# Gas_Sampler-9V_Boost.net
KiCad netlist of a schematic drawn in Altium Designer
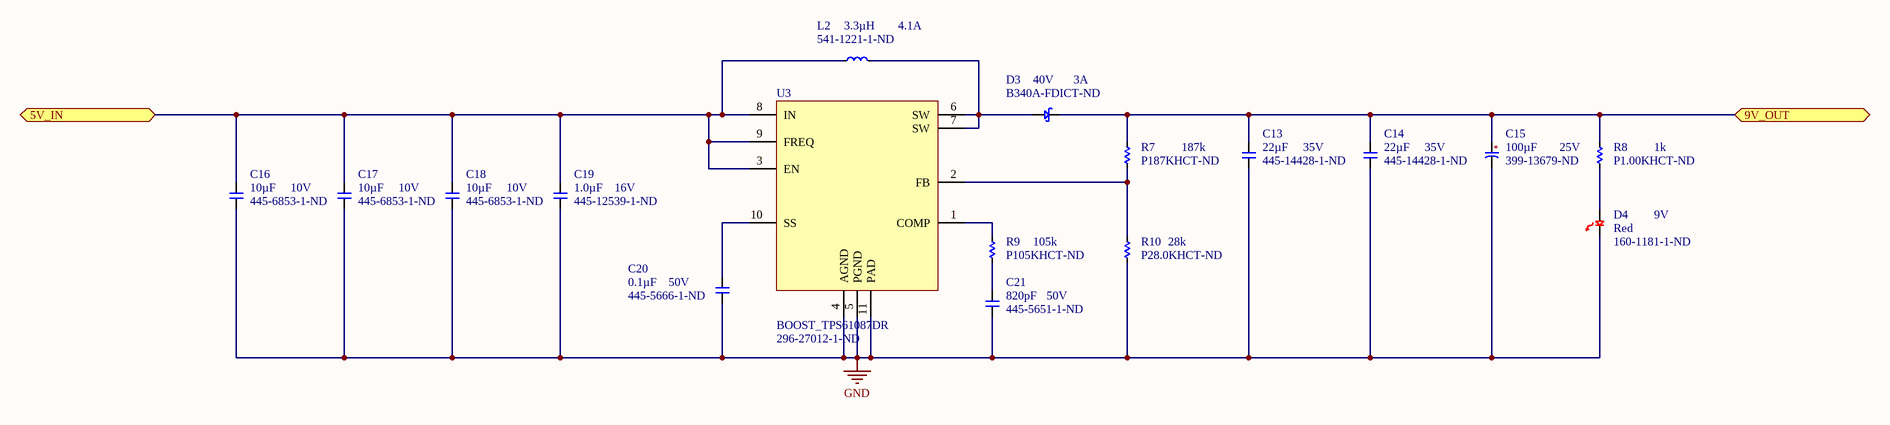
[diagram p0: Gas_Sampler-9V_Boost.SchDoc]

(export (version "E")
  (design (tool "Eeschema 10.0.6"))
  (components
    (comp (ref "C13")
      (value "22µF")
      (footprint "C0805")
      (description "CAP CER 22UF 35V 20% X5R 0805")
      (fields
        (field (name "MANUFACTURER") "TDK Corporation")
        (field (name "MANUFACTURER PART NUMBER") "C2012X5R1V226M125AC")
        (field (name "SUPPLIER PART NUMBER 1") "445-14428-1-ND")
        (field (name "VOLTAGE - RATED") "35V")
      )
      (libsource (lib "capacitor") (part "CAP_CER_0805_22UF_35V_20%_X5R"))
    )
    (comp (ref "C14")
      (value "22µF")
      (footprint "C0805")
      (description "CAP CER 22UF 35V 20% X5R 0805")
      (fields
        (field (name "MANUFACTURER") "TDK Corporation")
        (field (name "MANUFACTURER PART NUMBER") "C2012X5R1V226M125AC")
        (field (name "SUPPLIER PART NUMBER 1") "445-14428-1-ND")
        (field (name "VOLTAGE - RATED") "35V")
      )
      (libsource (lib "capacitor") (part "CAP_CER_0805_22UF_35V_20%_X5R"))
    )
    (comp (ref "C15")
      (value "100µF")
      (footprint "CAP_RADIAL_8MM_DIA_9MM_LEN_3.5MM_LEADSPACE")
      (description "CAP ALUM POLY 100UF 20% 25V T/H")
      (fields
        (field (name "MANUFACTURER") "KEMET")
        (field (name "MANUFACTURER PART NUMBER") "A750KK107M1EAAE040")
        (field (name "SUPPLIER PART NUMBER 1") "399-13679-ND")
        (field (name "VOLTAGE") "25V")
      )
      (libsource (lib "capacitor") (part "CAP_POLYMER_100UF_25V_20%_8X9MM_TH"))
    )
    (comp (ref "C16")
      (value "10µF")
      (footprint "C0603")
      (description "CAP CER 10UF 10V X5R 0603")
      (fields
        (field (name "MANUFACTURER") "TDK Corporation")
        (field (name "MANUFACTURER PART NUMBER") "C1608X5R1A106M080AC")
        (field (name "VOLTAGE - RATED") "10V")
        (field (name "SUPPLIER PART NUMBER 1") "445-6853-1-ND")
      )
      (libsource (lib "capacitor") (part "CAP_CER_0603_10UF_10V_20%_X5R"))
    )
    (comp (ref "C17")
      (value "10µF")
      (footprint "C0603")
      (description "CAP CER 10UF 10V X5R 0603")
      (fields
        (field (name "MANUFACTURER") "TDK Corporation")
        (field (name "MANUFACTURER PART NUMBER") "C1608X5R1A106M080AC")
        (field (name "VOLTAGE - RATED") "10V")
        (field (name "SUPPLIER PART NUMBER 1") "445-6853-1-ND")
      )
      (libsource (lib "capacitor") (part "CAP_CER_0603_10UF_10V_20%_X5R"))
    )
    (comp (ref "C18")
      (value "10µF")
      (footprint "C0603")
      (description "CAP CER 10UF 10V X5R 0603")
      (fields
        (field (name "MANUFACTURER") "TDK Corporation")
        (field (name "MANUFACTURER PART NUMBER") "C1608X5R1A106M080AC")
        (field (name "VOLTAGE - RATED") "10V")
        (field (name "SUPPLIER PART NUMBER 1") "445-6853-1-ND")
      )
      (libsource (lib "capacitor") (part "CAP_CER_0603_10UF_10V_20%_X5R"))
    )
    (comp (ref "C19")
      (value "1.0µF")
      (footprint "C0603")
      (description "CAP CER 1UF 16V 10% X7R 0603")
      (fields
        (field (name "MANUFACTURER") "TDK Corporation")
        (field (name "MANUFACTURER PART NUMBER") "CGA3E1X7R1C105K080AC")
        (field (name "SUPPLIER PART NUMBER 1") "445-12539-1-ND")
        (field (name "VOLTAGE - RATED") "16V")
      )
      (libsource (lib "capacitor") (part "CAP_CER_0603_1UF_16V_10%_X7R"))
    )
    (comp (ref "C20")
      (value "0.1µF")
      (footprint "C0603")
      (description "CAP CER 0.1UF 50V 10% X7R 0603")
      (fields
        (field (name "MANUFACTURER") "TDK Corporation")
        (field (name "MANUFACTURER PART NUMBER") "CGA3E2X7R1H104K080AA")
        (field (name "VOLTAGE - RATED") "50V")
        (field (name "SUPPLIER PART NUMBER 1") "445-5666-1-ND")
      )
      (libsource (lib "capacitor") (part "CAP_CER_0603_0.1UF_50V_10%_X7R"))
    )
    (comp (ref "C21")
      (value "820pF")
      (footprint "C0603")
      (description "CAP CER 820PF 50V C0G 0603")
      (fields
        (field (name "MANUFACTURER") "TDK Corporation")
        (field (name "MANUFACTURER PART NUMBER") "CGA3E2C0G1H821J080AA")
        (field (name "VOLTAGE - RATED") "50V")
        (field (name "SUPPLIER PART NUMBER 1") "445-5651-1-ND")
      )
      (libsource (lib "capacitor") (part "CAP_CER_0603_820PF_50V_5%_C0G/NP0"))
    )
    (comp (ref "D3")
      (value "SCHOTTKY_40V_3A_B340A-13-F")
      (footprint "SMA")
      (description "DIODE SCHOTTKY 3A 40V SMA")
      (fields
        (field (name "MANUFACTURER") "Diodes Inc")
        (field (name "MANUFACTURER PART NUMBER") "B340A-13-F")
        (field (name "SUPPLIER PART NUMBER 1") "B340A-FDICT-ND")
        (field (name "VOLTAGE - DC REVERSE (VR) (MAX)") "40V")
        (field (name "CURRENT - AVERAGE RECTIFIED (IO)") "3A")
      )
      (libsource (lib "diode") (part "SCHOTTKY_40V_3A_B340A-13-F"))
    )
    (comp (ref "D4")
      (value "9V")
      (footprint "LED_0603_RED")
      (description "LED RED CLEAR 0603 SMD")
      (fields
        (field (name "MANUFACTURER") "Lite-On Inc")
        (field (name "MANUFACTURER PART NUMBER") "LTST-C190CKT")
        (field (name "SUPPLIER PART NUMBER 1") "160-1181-1-ND")
        (field (name "COLOR") "Red")
      )
      (libsource (lib "diode") (part "LED_0603_RED_LR_LTST-C190CKT"))
    )
    (comp (ref "L2")
      (value "3.3µH")
      (footprint "INDUCTOR_IHLP2020_2MM_HEIGHT")
      (description "FIXED IND 3.3UH 4.1A 57.8 MOHM")
      (fields
        (field (name "MANUFACTURER") "Vishay Dale")
        (field (name "MANUFACTURER PART NUMBER") "IHLP2020BZER3R3M11")
        (field (name "CURRENT RATING") "4.1A")
        (field (name "SUPPLIER PART NUMBER 1") "541-1221-1-ND")
      )
      (libsource (lib "inductor") (part "IND_3.3UH_4.1A_IHLP2020BZER3R3M11"))
    )
    (comp (ref "R7")
      (value "187k")
      (footprint "R0603")
      (description "RES 187K OHM 1% 1/10W 0603")
      (fields
        (field (name "MANUFACTURER") "Panasonic Electronic Components")
        (field (name "MANUFACTURER PART NUMBER") "ERJ-3EKF1873V")
        (field (name "SUPPLIER PART NUMBER 1") "P187KHCT-ND")
      )
      (libsource (lib "resistor") (part "RES_0603_187K_OHMS_1/10W_1%"))
    )
    (comp (ref "R8")
      (value "1k")
      (footprint "R0603")
      (description "RES 1K OHM 1/10W 1% 0603 SMD")
      (fields
        (field (name "MANUFACTURER") "Panasonic Electronic Components")
        (field (name "MANUFACTURER PART NUMBER") "ERJ-3EKF1001V")
        (field (name "SUPPLIER PART NUMBER 1") "P1.00KHCT-ND")
      )
      (libsource (lib "resistor") (part "RES_0603_1K_OHM_1/10W_1%"))
    )
    (comp (ref "R9")
      (value "105k")
      (footprint "R0603")
      (description "RES 105K OHM 1% 1/10W 0603")
      (fields
        (field (name "MANUFACTURER") "Panasonic Electronic Components")
        (field (name "MANUFACTURER PART NUMBER") "ERJ-3EKF1053V")
        (field (name "SUPPLIER PART NUMBER 1") "P105KHCT-ND")
      )
      (libsource (lib "resistor") (part "RES_0603_105K_OHM_1/10W_1%"))
    )
    (comp (ref "R10")
      (value "28k")
      (footprint "R0603")
      (description "RES 28K OHM 1/10W 1% 0603 SMD")
      (fields
        (field (name "MANUFACTURER") "Panasonic Electronic Components")
        (field (name "MANUFACTURER PART NUMBER") "ERJ-3EKF2802V")
        (field (name "SUPPLIER PART NUMBER 1") "P28.0KHCT-ND")
      )
      (libsource (lib "resistor") (part "RES_0603_28K_OHM_1/10W_1%"))
    )
    (comp (ref "U3")
      (value "BOOST_TPS61087DR")
      (footprint "PVSON50P300X300X70-10N")
      (description "IC REG BOOST ADJ 3.2A 10SON")
      (fields
        (field (name "MANUFACTURER") "Texas Instruments")
        (field (name "MANUFACTURER PART NUMBER") "TPS61087DRCR")
        (field (name "SUPPLIER PART NUMBER 1") "296-27012-1-ND")
      )
      (libsource (lib "ic_pmic") (part "BOOST_TPS61087DR"))
    )
  )
  (nets
    (net (code "1") (name "/5V_IN") (class "Default")
      (node (ref "C16") (pin "1") (pintype "passive"))
      (node (ref "C17") (pin "1") (pintype "passive"))
      (node (ref "C18") (pin "1") (pintype "passive"))
      (node (ref "C19") (pin "1") (pintype "passive"))
      (node (ref "L2") (pin "1") (pintype "passive"))
      (node (ref "U3") (pin "3") (pinfunction "EN_3") (pintype "passive"))
      (node (ref "U3") (pin "8") (pinfunction "IN_8") (pintype "passive"))
      (node (ref "U3") (pin "9") (pinfunction "FREQ_9") (pintype "passive"))
    )
    (net (code "2") (name "/9V_OUT") (class "Default")
      (node (ref "C13") (pin "1") (pintype "passive"))
      (node (ref "C14") (pin "1") (pintype "passive"))
      (node (ref "C15") (pin "1") (pintype "passive"))
      (node (ref "D3") (pin "2") (pintype "passive"))
      (node (ref "R7") (pin "2") (pintype "passive"))
      (node (ref "R8") (pin "2") (pintype "passive"))
    )
    (net (code "3") (name "GND") (class "Default")
      (node (ref "C13") (pin "2") (pintype "passive"))
      (node (ref "C14") (pin "2") (pintype "passive"))
      (node (ref "C15") (pin "2") (pintype "passive"))
      (node (ref "C16") (pin "2") (pintype "passive"))
      (node (ref "C17") (pin "2") (pintype "passive"))
      (node (ref "C18") (pin "2") (pintype "passive"))
      (node (ref "C19") (pin "2") (pintype "passive"))
      (node (ref "C20") (pin "2") (pintype "passive"))
      (node (ref "C21") (pin "2") (pintype "passive"))
      (node (ref "D4") (pin "2") (pinfunction "CATHODE_2") (pintype "passive"))
      (node (ref "R10") (pin "1") (pintype "passive"))
      (node (ref "U3") (pin "11") (pinfunction "PAD_11") (pintype "passive"))
      (node (ref "U3") (pin "4") (pinfunction "AGND_4") (pintype "passive"))
      (node (ref "U3") (pin "5") (pinfunction "PGND_5") (pintype "passive"))
    )
    (net (code "4") (name "Net-(C21-Pad1)") (class "Default")
      (node (ref "C21") (pin "1") (pintype "passive"))
      (node (ref "R9") (pin "1") (pintype "passive"))
    )
    (net (code "5") (name "Net-(D3-Pad1)") (class "Default")
      (node (ref "D3") (pin "1") (pintype "passive"))
      (node (ref "L2") (pin "2") (pintype "passive"))
      (node (ref "U3") (pin "6") (pinfunction "SW_6") (pintype "passive"))
      (node (ref "U3") (pin "7") (pinfunction "SW_7") (pintype "passive"))
    )
    (net (code "6") (name "Net-(D4-ANODE)") (class "Default")
      (node (ref "D4") (pin "1") (pinfunction "ANODE_1") (pintype "passive"))
      (node (ref "R8") (pin "1") (pintype "passive"))
    )
    (net (code "7") (name "Net-(U3-COMP)") (class "Default")
      (node (ref "R9") (pin "2") (pintype "passive"))
      (node (ref "U3") (pin "1") (pinfunction "COMP_1") (pintype "passive"))
    )
    (net (code "8") (name "Net-(U3-FB)") (class "Default")
      (node (ref "R10") (pin "2") (pintype "passive"))
      (node (ref "R7") (pin "1") (pintype "passive"))
      (node (ref "U3") (pin "2") (pinfunction "FB_2") (pintype "passive"))
    )
    (net (code "9") (name "Net-(U3-SS)") (class "Default")
      (node (ref "C20") (pin "1") (pintype "passive"))
      (node (ref "U3") (pin "10") (pinfunction "SS_10") (pintype "passive"))
    )
  )
)
